# IOIO.net
KiCad netlist of a schematic drawn in EAGLE
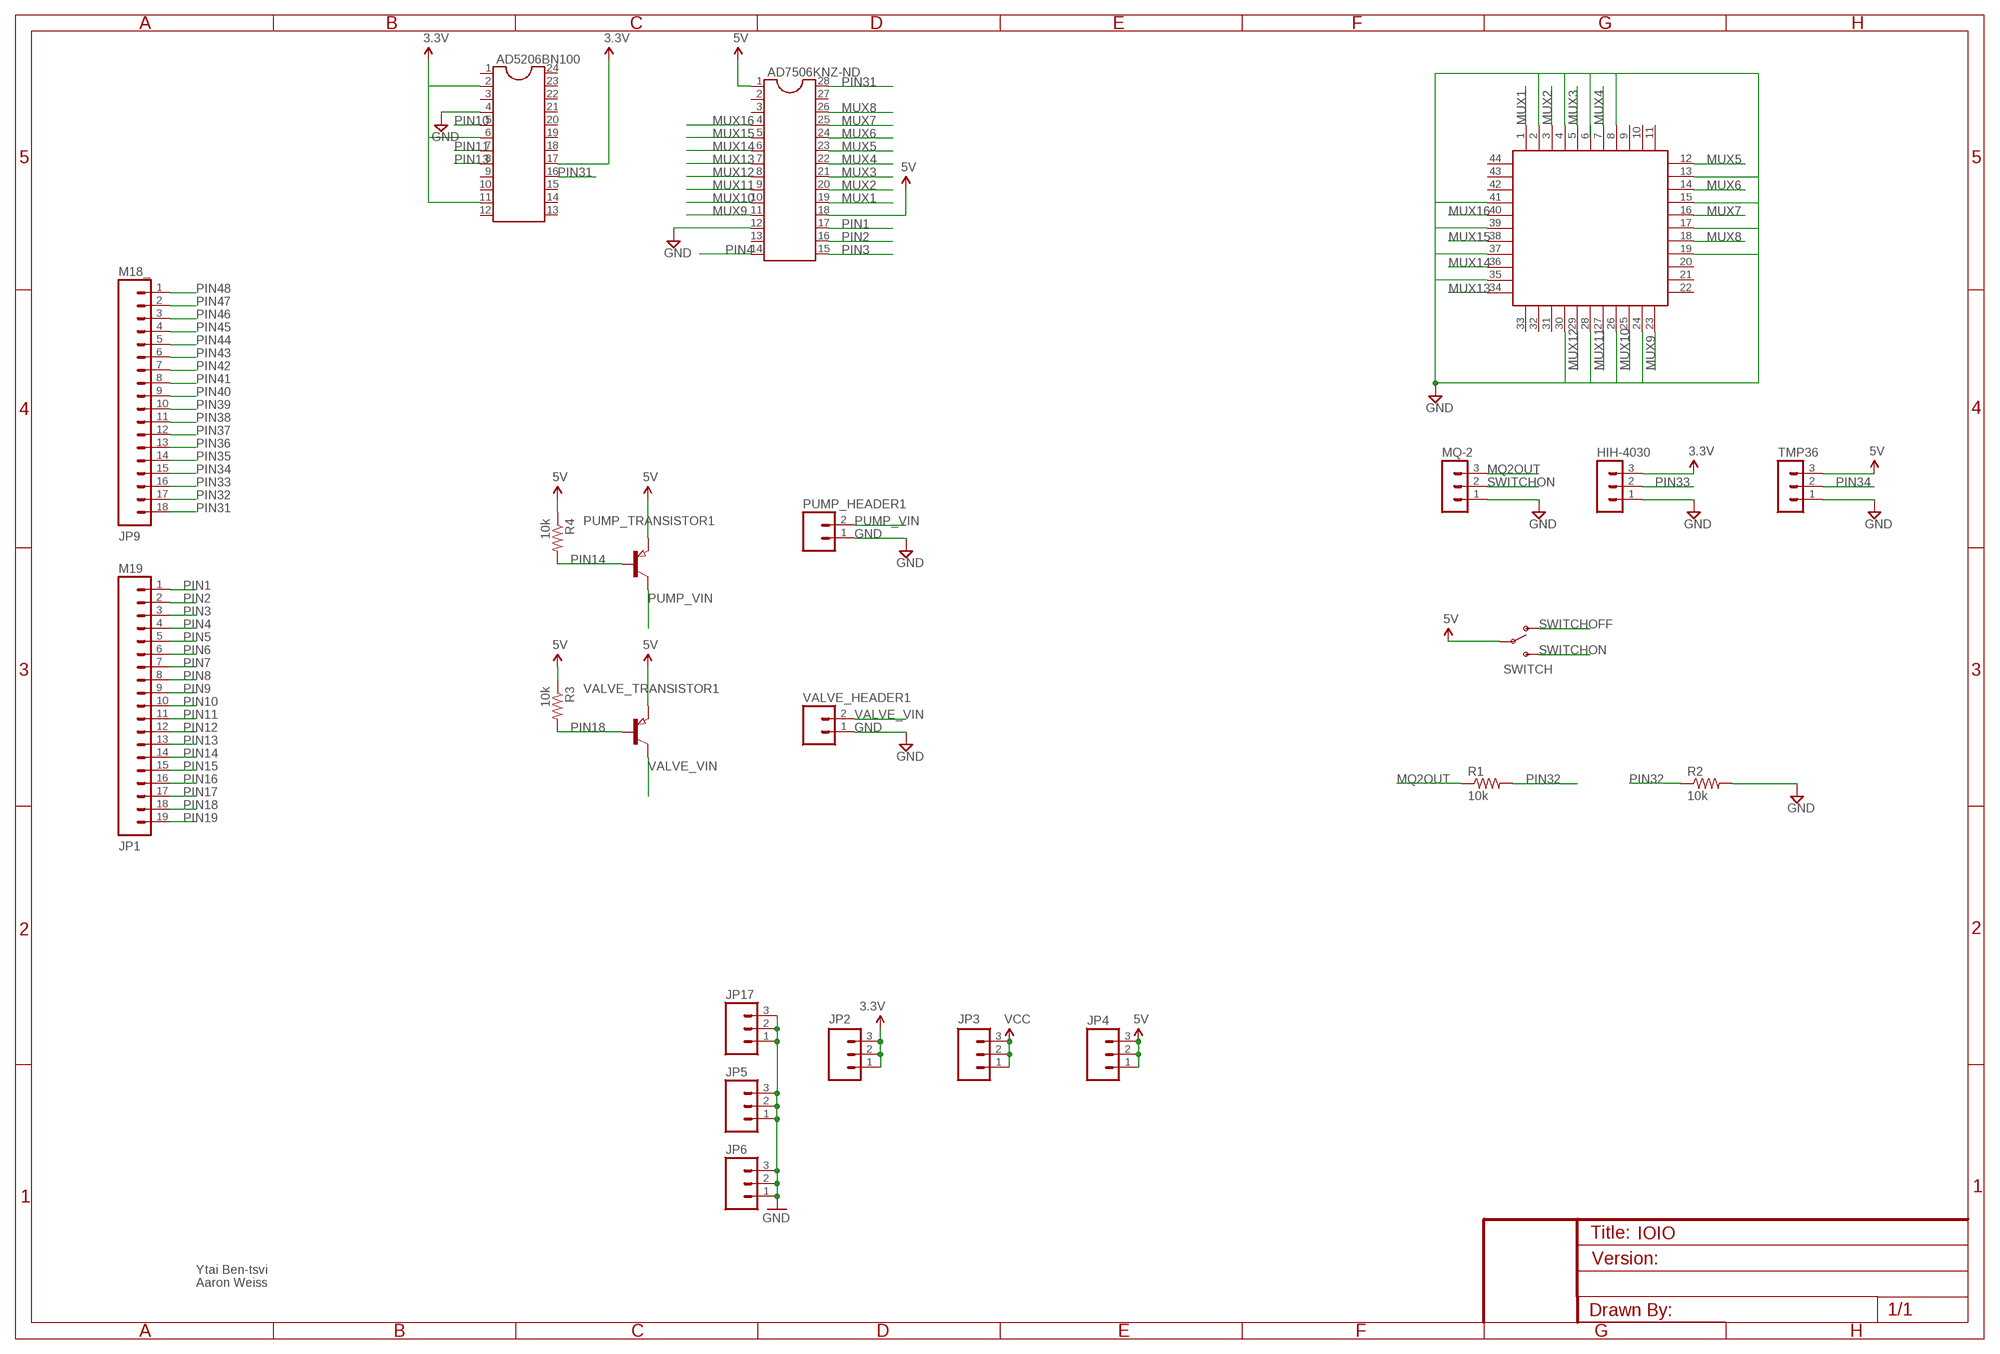
[diagram p0: schematic, sheet 1]

(export (version "E")
  (design (tool "Eeschema 10.0.6"))
  (components
    (comp (ref "AD5206BN100")
      (value "DIL24-3")
      (footprint "eagle-import:DIL24-3")
      (libsource (lib "eagle-import") (part "DIL24-3"))
    )
    (comp (ref "AD7506KNZ-ND")
      (value "DIL28")
      (footprint "eagle-import:DIL28-6")
      (libsource (lib "eagle-import") (part "DIL28"))
    )
    (comp (ref "HIH-4030")
      (value "MA03-1")
      (footprint "eagle-import:MA03-1")
      (libsource (lib "eagle-import") (part "MA03-1"))
    )
    (comp (ref "JP1")
      (value "M19")
      (footprint "eagle-import:1X19")
      (libsource (lib "eagle-import") (part "M19"))
    )
    (comp (ref "JP2")
      (value "M03PTH")
      (footprint "eagle-import:1X03")
      (libsource (lib "eagle-import") (part "M03PTH"))
    )
    (comp (ref "JP3")
      (value "M03PTH")
      (footprint "eagle-import:1X03")
      (libsource (lib "eagle-import") (part "M03PTH"))
    )
    (comp (ref "JP4")
      (value "M03PTH")
      (footprint "eagle-import:1X03")
      (libsource (lib "eagle-import") (part "M03PTH"))
    )
    (comp (ref "JP5")
      (value "M03PTH")
      (footprint "eagle-import:1X03")
      (libsource (lib "eagle-import") (part "M03PTH"))
    )
    (comp (ref "JP6")
      (value "M03PTH")
      (footprint "eagle-import:1X03")
      (libsource (lib "eagle-import") (part "M03PTH"))
    )
    (comp (ref "JP9")
      (value "M18_")
      (footprint "eagle-import:1X18")
      (libsource (lib "eagle-import") (part "M18_"))
    )
    (comp (ref "JP17")
      (value "M03PTH")
      (footprint "eagle-import:1X03")
      (libsource (lib "eagle-import") (part "M03PTH"))
    )
    (comp (ref "MQ-2")
      (value "MA03-1")
      (footprint "eagle-import:MA03-1")
      (libsource (lib "eagle-import") (part "MA03-1"))
    )
    (comp (ref "PUMP_HEADER1")
      (value "M02PTH")
      (footprint "eagle-import:1X02")
      (libsource (lib "eagle-import") (part "M02PTH"))
    )
    (comp (ref "PUMP_TRANSISTOR1")
      (value "PNP-TRANSISTOR_SOT23")
      (footprint "eagle-import:SOT23")
      (libsource (lib "eagle-import") (part "PNP-TRANSISTOR_SOT23"))
    )
    (comp (ref "R1")
      (value "10k")
      (footprint "eagle-import:0207_7")
      (libsource (lib "eagle-import") (part "R-US_0207/7"))
    )
    (comp (ref "R2")
      (value "10k")
      (footprint "eagle-import:0207_7")
      (libsource (lib "eagle-import") (part "R-US_0207/7"))
    )
    (comp (ref "R3")
      (value "10k")
      (footprint "eagle-import:M2012")
      (libsource (lib "eagle-import") (part "R-US_M2012"))
    )
    (comp (ref "R4")
      (value "10k")
      (footprint "eagle-import:M2012")
      (libsource (lib "eagle-import") (part "R-US_M2012"))
    )
    (comp (ref "SWITCH")
      (value "SWITCH-SPSTPTH")
      (footprint "eagle-import:SWITCH-SPDT")
      (libsource (lib "eagle-import") (part "SWITCH-SPSTPTH"))
    )
    (comp (ref "TMP36")
      (value "MA03-1")
      (footprint "eagle-import:MA03-1")
      (libsource (lib "eagle-import") (part "MA03-1"))
    )
    (comp (ref "U$1")
      (value "S44")
      (footprint "eagle-import:S44")
      (libsource (lib "eagle-import") (part "S44"))
    )
    (comp (ref "VALVE_HEADER1")
      (value "M02PTH")
      (footprint "eagle-import:1X02")
      (libsource (lib "eagle-import") (part "M02PTH"))
    )
    (comp (ref "VALVE_TRANSISTOR1")
      (value "PNP-TRANSISTOR_SOT23")
      (footprint "eagle-import:SOT23")
      (libsource (lib "eagle-import") (part "PNP-TRANSISTOR_SOT23"))
    )
  )
  (nets
    (net (code "1") (name "/MQ2OUT") (class "Default")
      (node (ref "MQ-2") (pin "3") (pinfunction "3_3") (pintype "passive"))
      (node (ref "R1") (pin "1") (pinfunction "1_1") (pintype "passive"))
    )
    (net (code "2") (name "/MUX1") (class "Default")
      (node (ref "AD7506KNZ-ND") (pin "19") (pinfunction "19_19") (pintype "passive"))
      (node (ref "U$1") (pin "1") (pinfunction "P$1_1") (pintype "bidirectional"))
    )
    (net (code "3") (name "/MUX2") (class "Default")
      (node (ref "AD7506KNZ-ND") (pin "20") (pinfunction "20_20") (pintype "passive"))
      (node (ref "U$1") (pin "3") (pinfunction "P$3_3") (pintype "bidirectional"))
    )
    (net (code "4") (name "/MUX3") (class "Default")
      (node (ref "AD7506KNZ-ND") (pin "21") (pinfunction "21_21") (pintype "passive"))
      (node (ref "U$1") (pin "5") (pinfunction "P$5_5") (pintype "bidirectional"))
    )
    (net (code "5") (name "/MUX4") (class "Default")
      (node (ref "AD7506KNZ-ND") (pin "22") (pinfunction "22_22") (pintype "passive"))
      (node (ref "U$1") (pin "7") (pinfunction "P$7_7") (pintype "bidirectional"))
    )
    (net (code "6") (name "/MUX5") (class "Default")
      (node (ref "AD7506KNZ-ND") (pin "23") (pinfunction "23_23") (pintype "passive"))
      (node (ref "U$1") (pin "12") (pinfunction "P$12_12") (pintype "bidirectional"))
    )
    (net (code "7") (name "/MUX6") (class "Default")
      (node (ref "AD7506KNZ-ND") (pin "24") (pinfunction "24_24") (pintype "passive"))
      (node (ref "U$1") (pin "14") (pinfunction "P$14_14") (pintype "bidirectional"))
    )
    (net (code "8") (name "/MUX7") (class "Default")
      (node (ref "AD7506KNZ-ND") (pin "25") (pinfunction "25_25") (pintype "passive"))
      (node (ref "U$1") (pin "16") (pinfunction "P$16_16") (pintype "bidirectional"))
    )
    (net (code "9") (name "/MUX8") (class "Default")
      (node (ref "AD7506KNZ-ND") (pin "26") (pinfunction "26_26") (pintype "passive"))
      (node (ref "U$1") (pin "18") (pinfunction "P$18_18") (pintype "bidirectional"))
    )
    (net (code "10") (name "/MUX9") (class "Default")
      (node (ref "AD7506KNZ-ND") (pin "11") (pinfunction "11_11") (pintype "passive"))
      (node (ref "U$1") (pin "23") (pinfunction "P$23_23") (pintype "bidirectional"))
    )
    (net (code "11") (name "/MUX10") (class "Default")
      (node (ref "AD7506KNZ-ND") (pin "10") (pinfunction "10_10") (pintype "passive"))
      (node (ref "U$1") (pin "25") (pinfunction "P$25_25") (pintype "bidirectional"))
    )
    (net (code "12") (name "/MUX11") (class "Default")
      (node (ref "AD7506KNZ-ND") (pin "9") (pinfunction "9_9") (pintype "passive"))
      (node (ref "U$1") (pin "27") (pinfunction "P$27_27") (pintype "bidirectional"))
    )
    (net (code "13") (name "/MUX12") (class "Default")
      (node (ref "AD7506KNZ-ND") (pin "8") (pinfunction "8_8") (pintype "passive"))
      (node (ref "U$1") (pin "29") (pinfunction "P$29_29") (pintype "bidirectional"))
    )
    (net (code "14") (name "/MUX13") (class "Default")
      (node (ref "AD7506KNZ-ND") (pin "7") (pinfunction "7_7") (pintype "passive"))
      (node (ref "U$1") (pin "34") (pinfunction "P$34_34") (pintype "bidirectional"))
    )
    (net (code "15") (name "/MUX14") (class "Default")
      (node (ref "AD7506KNZ-ND") (pin "6") (pinfunction "6_6") (pintype "passive"))
      (node (ref "U$1") (pin "36") (pinfunction "P$36_36") (pintype "bidirectional"))
    )
    (net (code "16") (name "/MUX15") (class "Default")
      (node (ref "AD7506KNZ-ND") (pin "5") (pinfunction "5_5") (pintype "passive"))
      (node (ref "U$1") (pin "38") (pinfunction "P$38_38") (pintype "bidirectional"))
    )
    (net (code "17") (name "/MUX16") (class "Default")
      (node (ref "AD7506KNZ-ND") (pin "4") (pinfunction "4_4") (pintype "passive"))
      (node (ref "U$1") (pin "40") (pinfunction "P$40_40") (pintype "bidirectional"))
    )
    (net (code "18") (name "/PIN1") (class "Default")
      (node (ref "AD7506KNZ-ND") (pin "17") (pinfunction "17_17") (pintype "passive"))
      (node (ref "JP1") (pin "1") (pinfunction "1_1") (pintype "passive"))
    )
    (net (code "19") (name "/PIN2") (class "Default")
      (node (ref "AD7506KNZ-ND") (pin "16") (pinfunction "16_16") (pintype "passive"))
      (node (ref "JP1") (pin "2") (pinfunction "2_2") (pintype "passive"))
    )
    (net (code "20") (name "/PIN3") (class "Default")
      (node (ref "AD7506KNZ-ND") (pin "15") (pinfunction "15_15") (pintype "passive"))
      (node (ref "JP1") (pin "3") (pinfunction "3_3") (pintype "passive"))
    )
    (net (code "21") (name "/PIN4") (class "Default")
      (node (ref "AD7506KNZ-ND") (pin "14") (pinfunction "14_14") (pintype "passive"))
      (node (ref "JP1") (pin "4") (pinfunction "4_4") (pintype "passive"))
    )
    (net (code "22") (name "/PIN5") (class "Default")
      (node (ref "JP1") (pin "5") (pinfunction "5_5") (pintype "passive"))
    )
    (net (code "23") (name "/PIN6") (class "Default")
      (node (ref "JP1") (pin "6") (pinfunction "6_6") (pintype "passive"))
    )
    (net (code "24") (name "/PIN7") (class "Default")
      (node (ref "JP1") (pin "7") (pinfunction "7_7") (pintype "passive"))
    )
    (net (code "25") (name "/PIN8") (class "Default")
      (node (ref "JP1") (pin "8") (pinfunction "8_8") (pintype "passive"))
    )
    (net (code "26") (name "/PIN9") (class "Default")
      (node (ref "JP1") (pin "9") (pinfunction "9_9") (pintype "passive"))
    )
    (net (code "27") (name "/PIN10") (class "Default")
      (node (ref "AD5206BN100") (pin "5") (pinfunction "5_5") (pintype "passive"))
      (node (ref "JP1") (pin "10") (pinfunction "10_10") (pintype "passive"))
    )
    (net (code "28") (name "/PIN11") (class "Default")
      (node (ref "AD5206BN100") (pin "7") (pinfunction "7_7") (pintype "passive"))
      (node (ref "JP1") (pin "11") (pinfunction "11_11") (pintype "passive"))
    )
    (net (code "29") (name "/PIN12") (class "Default")
      (node (ref "JP1") (pin "12") (pinfunction "12_12") (pintype "passive"))
    )
    (net (code "30") (name "/PIN13") (class "Default")
      (node (ref "AD5206BN100") (pin "8") (pinfunction "8_8") (pintype "passive"))
      (node (ref "JP1") (pin "13") (pinfunction "13_13") (pintype "passive"))
    )
    (net (code "31") (name "/PIN14") (class "Default")
      (node (ref "JP1") (pin "14") (pinfunction "14_14") (pintype "passive"))
      (node (ref "PUMP_TRANSISTOR1") (pin "1") (pinfunction "B_1") (pintype "passive"))
      (node (ref "R4") (pin "2") (pinfunction "2_2") (pintype "passive"))
    )
    (net (code "32") (name "/PIN15") (class "Default")
      (node (ref "JP1") (pin "15") (pinfunction "15_15") (pintype "passive"))
    )
    (net (code "33") (name "/PIN16") (class "Default")
      (node (ref "JP1") (pin "16") (pinfunction "16_16") (pintype "passive"))
    )
    (net (code "34") (name "/PIN17") (class "Default")
      (node (ref "JP1") (pin "17") (pinfunction "17_17") (pintype "passive"))
    )
    (net (code "35") (name "/PIN18") (class "Default")
      (node (ref "JP1") (pin "18") (pinfunction "18_18") (pintype "passive"))
      (node (ref "R3") (pin "2") (pinfunction "2_2") (pintype "passive"))
      (node (ref "VALVE_TRANSISTOR1") (pin "1") (pinfunction "B_1") (pintype "passive"))
    )
    (net (code "36") (name "/PIN19") (class "Default")
      (node (ref "JP1") (pin "19") (pinfunction "19_19") (pintype "passive"))
    )
    (net (code "37") (name "/PIN31") (class "Default")
      (node (ref "AD5206BN100") (pin "16") (pinfunction "16_16") (pintype "passive"))
      (node (ref "AD7506KNZ-ND") (pin "28") (pinfunction "28_28") (pintype "passive"))
      (node (ref "JP9") (pin "18") (pinfunction "18_18") (pintype "passive"))
    )
    (net (code "38") (name "/PIN32") (class "Default")
      (node (ref "JP9") (pin "17") (pinfunction "17_17") (pintype "passive"))
      (node (ref "R1") (pin "2") (pinfunction "2_2") (pintype "passive"))
      (node (ref "R2") (pin "1") (pinfunction "1_1") (pintype "passive"))
    )
    (net (code "39") (name "/PIN33") (class "Default")
      (node (ref "HIH-4030") (pin "2") (pinfunction "2_2") (pintype "passive"))
      (node (ref "JP9") (pin "16") (pinfunction "16_16") (pintype "passive"))
    )
    (net (code "40") (name "/PIN34") (class "Default")
      (node (ref "JP9") (pin "15") (pinfunction "15_15") (pintype "passive"))
      (node (ref "TMP36") (pin "2") (pinfunction "2_2") (pintype "passive"))
    )
    (net (code "41") (name "/PIN35") (class "Default")
      (node (ref "JP9") (pin "14") (pinfunction "14_14") (pintype "passive"))
    )
    (net (code "42") (name "/PIN36") (class "Default")
      (node (ref "JP9") (pin "13") (pinfunction "13_13") (pintype "passive"))
    )
    (net (code "43") (name "/PIN37") (class "Default")
      (node (ref "JP9") (pin "12") (pinfunction "12_12") (pintype "passive"))
    )
    (net (code "44") (name "/PIN38") (class "Default")
      (node (ref "JP9") (pin "11") (pinfunction "11_11") (pintype "passive"))
    )
    (net (code "45") (name "/PIN39") (class "Default")
      (node (ref "JP9") (pin "10") (pinfunction "10_10") (pintype "passive"))
    )
    (net (code "46") (name "/PIN40") (class "Default")
      (node (ref "JP9") (pin "9") (pinfunction "9_9") (pintype "passive"))
    )
    (net (code "47") (name "/PIN41") (class "Default")
      (node (ref "JP9") (pin "8") (pinfunction "8_8") (pintype "passive"))
    )
    (net (code "48") (name "/PIN42") (class "Default")
      (node (ref "JP9") (pin "7") (pinfunction "7_7") (pintype "passive"))
    )
    (net (code "49") (name "/PIN43") (class "Default")
      (node (ref "JP9") (pin "6") (pinfunction "6_6") (pintype "passive"))
    )
    (net (code "50") (name "/PIN44") (class "Default")
      (node (ref "JP9") (pin "5") (pinfunction "5_5") (pintype "passive"))
    )
    (net (code "51") (name "/PIN45") (class "Default")
      (node (ref "JP9") (pin "4") (pinfunction "4_4") (pintype "passive"))
    )
    (net (code "52") (name "/PIN46") (class "Default")
      (node (ref "JP9") (pin "3") (pinfunction "3_3") (pintype "passive"))
    )
    (net (code "53") (name "/PIN47") (class "Default")
      (node (ref "JP9") (pin "2") (pinfunction "2_2") (pintype "passive"))
    )
    (net (code "54") (name "/PIN48") (class "Default")
      (node (ref "JP9") (pin "1") (pinfunction "1_1") (pintype "passive"))
    )
    (net (code "55") (name "/PUMP_VIN") (class "Default")
      (node (ref "PUMP_HEADER1") (pin "2") (pinfunction "2_2") (pintype "passive"))
      (node (ref "PUMP_TRANSISTOR1") (pin "3") (pinfunction "C_3") (pintype "passive"))
    )
    (net (code "56") (name "/SWITCHOFF") (class "Default")
      (node (ref "SWITCH") (pin "1") (pinfunction "O_1") (pintype "passive"))
    )
    (net (code "57") (name "/SWITCHON") (class "Default")
      (node (ref "MQ-2") (pin "2") (pinfunction "2_2") (pintype "passive"))
      (node (ref "SWITCH") (pin "3") (pinfunction "S_3") (pintype "passive"))
    )
    (net (code "58") (name "/VALVE_VIN") (class "Default")
      (node (ref "VALVE_HEADER1") (pin "2") (pinfunction "2_2") (pintype "passive"))
      (node (ref "VALVE_TRANSISTOR1") (pin "3") (pinfunction "C_3") (pintype "passive"))
    )
    (net (code "59") (name "3.3V") (class "Default")
      (node (ref "AD5206BN100") (pin "11") (pinfunction "11_11") (pintype "passive"))
      (node (ref "AD5206BN100") (pin "17") (pinfunction "17_17") (pintype "passive"))
      (node (ref "AD5206BN100") (pin "2") (pinfunction "2_2") (pintype "passive"))
      (node (ref "AD5206BN100") (pin "6") (pinfunction "6_6") (pintype "passive"))
      (node (ref "HIH-4030") (pin "3") (pinfunction "3_3") (pintype "passive"))
      (node (ref "JP2") (pin "1") (pinfunction "1_1") (pintype "passive"))
      (node (ref "JP2") (pin "2") (pinfunction "2_2") (pintype "passive"))
      (node (ref "JP2") (pin "3") (pinfunction "3_3") (pintype "passive"))
    )
    (net (code "60") (name "5V") (class "Default")
      (node (ref "AD7506KNZ-ND") (pin "1") (pinfunction "1_1") (pintype "passive"))
      (node (ref "AD7506KNZ-ND") (pin "18") (pinfunction "18_18") (pintype "passive"))
      (node (ref "JP4") (pin "1") (pinfunction "1_1") (pintype "passive"))
      (node (ref "JP4") (pin "2") (pinfunction "2_2") (pintype "passive"))
      (node (ref "JP4") (pin "3") (pinfunction "3_3") (pintype "passive"))
      (node (ref "PUMP_TRANSISTOR1") (pin "2") (pinfunction "E_2") (pintype "passive"))
      (node (ref "R3") (pin "1") (pinfunction "1_1") (pintype "passive"))
      (node (ref "R4") (pin "1") (pinfunction "1_1") (pintype "passive"))
      (node (ref "SWITCH") (pin "2") (pinfunction "P_2") (pintype "passive"))
      (node (ref "TMP36") (pin "3") (pinfunction "3_3") (pintype "passive"))
      (node (ref "VALVE_TRANSISTOR1") (pin "2") (pinfunction "E_2") (pintype "passive"))
    )
    (net (code "61") (name "GND") (class "Default")
      (node (ref "AD5206BN100") (pin "4") (pinfunction "4_4") (pintype "passive"))
      (node (ref "AD7506KNZ-ND") (pin "12") (pinfunction "12_12") (pintype "passive"))
      (node (ref "HIH-4030") (pin "1") (pinfunction "1_1") (pintype "passive"))
      (node (ref "JP17") (pin "1") (pinfunction "1_1") (pintype "passive"))
      (node (ref "JP17") (pin "2") (pinfunction "2_2") (pintype "passive"))
      (node (ref "JP17") (pin "3") (pinfunction "3_3") (pintype "passive"))
      (node (ref "JP5") (pin "1") (pinfunction "1_1") (pintype "passive"))
      (node (ref "JP5") (pin "2") (pinfunction "2_2") (pintype "passive"))
      (node (ref "JP5") (pin "3") (pinfunction "3_3") (pintype "passive"))
      (node (ref "JP6") (pin "1") (pinfunction "1_1") (pintype "passive"))
      (node (ref "JP6") (pin "2") (pinfunction "2_2") (pintype "passive"))
      (node (ref "JP6") (pin "3") (pinfunction "3_3") (pintype "passive"))
      (node (ref "MQ-2") (pin "1") (pinfunction "1_1") (pintype "passive"))
      (node (ref "PUMP_HEADER1") (pin "1") (pinfunction "1_1") (pintype "passive"))
      (node (ref "R2") (pin "2") (pinfunction "2_2") (pintype "passive"))
      (node (ref "TMP36") (pin "1") (pinfunction "1_1") (pintype "passive"))
      (node (ref "U$1") (pin "13") (pinfunction "P$13_13") (pintype "bidirectional"))
      (node (ref "U$1") (pin "15") (pinfunction "P$15_15") (pintype "bidirectional"))
      (node (ref "U$1") (pin "17") (pinfunction "P$17_17") (pintype "bidirectional"))
      (node (ref "U$1") (pin "19") (pinfunction "P$19_19") (pintype "bidirectional"))
      (node (ref "U$1") (pin "2") (pinfunction "P$2_2") (pintype "bidirectional"))
      (node (ref "U$1") (pin "24") (pinfunction "P$24_24") (pintype "bidirectional"))
      (node (ref "U$1") (pin "26") (pinfunction "P$26_26") (pintype "bidirectional"))
      (node (ref "U$1") (pin "28") (pinfunction "P$28_28") (pintype "bidirectional"))
      (node (ref "U$1") (pin "30") (pinfunction "P$30_30") (pintype "bidirectional"))
      (node (ref "U$1") (pin "35") (pinfunction "P$35_35") (pintype "bidirectional"))
      (node (ref "U$1") (pin "37") (pinfunction "P$37_37") (pintype "bidirectional"))
      (node (ref "U$1") (pin "39") (pinfunction "P$39_39") (pintype "bidirectional"))
      (node (ref "U$1") (pin "4") (pinfunction "P$4_4") (pintype "bidirectional"))
      (node (ref "U$1") (pin "41") (pinfunction "P$41_41") (pintype "bidirectional"))
      (node (ref "U$1") (pin "8") (pinfunction "P$8_8") (pintype "bidirectional"))
      (node (ref "VALVE_HEADER1") (pin "1") (pinfunction "1_1") (pintype "passive"))
    )
    (net (code "62") (name "VCC") (class "Default")
      (node (ref "JP3") (pin "1") (pinfunction "1_1") (pintype "passive"))
      (node (ref "JP3") (pin "2") (pinfunction "2_2") (pintype "passive"))
      (node (ref "JP3") (pin "3") (pinfunction "3_3") (pintype "passive"))
    )
    (net (code "63") (name "unconnected-(AD5206BN100-Pad1)") (class "Default")
      (node (ref "AD5206BN100") (pin "1") (pinfunction "1_1") (pintype "passive"))
    )
    (net (code "64") (name "unconnected-(AD5206BN100-Pad3)") (class "Default")
      (node (ref "AD5206BN100") (pin "3") (pinfunction "3_3") (pintype "passive"))
    )
    (net (code "65") (name "unconnected-(AD5206BN100-Pad9)") (class "Default")
      (node (ref "AD5206BN100") (pin "9") (pinfunction "9_9") (pintype "passive"))
    )
    (net (code "66") (name "unconnected-(AD5206BN100-Pad10)") (class "Default")
      (node (ref "AD5206BN100") (pin "10") (pinfunction "10_10") (pintype "passive"))
    )
    (net (code "67") (name "unconnected-(AD5206BN100-Pad12)") (class "Default")
      (node (ref "AD5206BN100") (pin "12") (pinfunction "12_12") (pintype "passive"))
    )
    (net (code "68") (name "unconnected-(AD5206BN100-Pad13)") (class "Default")
      (node (ref "AD5206BN100") (pin "13") (pinfunction "13_13") (pintype "passive"))
    )
    (net (code "69") (name "unconnected-(AD5206BN100-Pad14)") (class "Default")
      (node (ref "AD5206BN100") (pin "14") (pinfunction "14_14") (pintype "passive"))
    )
    (net (code "70") (name "unconnected-(AD5206BN100-Pad15)") (class "Default")
      (node (ref "AD5206BN100") (pin "15") (pinfunction "15_15") (pintype "passive"))
    )
    (net (code "71") (name "unconnected-(AD5206BN100-Pad18)") (class "Default")
      (node (ref "AD5206BN100") (pin "18") (pinfunction "18_18") (pintype "passive"))
    )
    (net (code "72") (name "unconnected-(AD5206BN100-Pad19)") (class "Default")
      (node (ref "AD5206BN100") (pin "19") (pinfunction "19_19") (pintype "passive"))
    )
    (net (code "73") (name "unconnected-(AD5206BN100-Pad20)") (class "Default")
      (node (ref "AD5206BN100") (pin "20") (pinfunction "20_20") (pintype "passive"))
    )
    (net (code "74") (name "unconnected-(AD5206BN100-Pad21)") (class "Default")
      (node (ref "AD5206BN100") (pin "21") (pinfunction "21_21") (pintype "passive"))
    )
    (net (code "75") (name "unconnected-(AD5206BN100-Pad22)") (class "Default")
      (node (ref "AD5206BN100") (pin "22") (pinfunction "22_22") (pintype "passive"))
    )
    (net (code "76") (name "unconnected-(AD5206BN100-Pad23)") (class "Default")
      (node (ref "AD5206BN100") (pin "23") (pinfunction "23_23") (pintype "passive"))
    )
    (net (code "77") (name "unconnected-(AD5206BN100-Pad24)") (class "Default")
      (node (ref "AD5206BN100") (pin "24") (pinfunction "24_24") (pintype "passive"))
    )
    (net (code "78") (name "unconnected-(AD7506KNZ-ND-Pad2)") (class "Default")
      (node (ref "AD7506KNZ-ND") (pin "2") (pinfunction "2_2") (pintype "passive"))
    )
    (net (code "79") (name "unconnected-(AD7506KNZ-ND-Pad3)") (class "Default")
      (node (ref "AD7506KNZ-ND") (pin "3") (pinfunction "3_3") (pintype "passive"))
    )
    (net (code "80") (name "unconnected-(AD7506KNZ-ND-Pad13)") (class "Default")
      (node (ref "AD7506KNZ-ND") (pin "13") (pinfunction "13_13") (pintype "passive"))
    )
    (net (code "81") (name "unconnected-(AD7506KNZ-ND-Pad27)") (class "Default")
      (node (ref "AD7506KNZ-ND") (pin "27") (pinfunction "27_27") (pintype "passive"))
    )
    (net (code "82") (name "unconnected-(U$1-P$6-Pad6)") (class "Default")
      (node (ref "U$1") (pin "6") (pinfunction "P$6_6") (pintype "bidirectional"))
    )
    (net (code "83") (name "unconnected-(U$1-P$9-Pad9)") (class "Default")
      (node (ref "U$1") (pin "9") (pinfunction "P$9_9") (pintype "bidirectional"))
    )
    (net (code "84") (name "unconnected-(U$1-P$10-Pad10)") (class "Default")
      (node (ref "U$1") (pin "10") (pinfunction "P$10_10") (pintype "bidirectional"))
    )
    (net (code "85") (name "unconnected-(U$1-P$11-Pad11)") (class "Default")
      (node (ref "U$1") (pin "11") (pinfunction "P$11_11") (pintype "bidirectional"))
    )
    (net (code "86") (name "unconnected-(U$1-P$20-Pad20)") (class "Default")
      (node (ref "U$1") (pin "20") (pinfunction "P$20_20") (pintype "bidirectional"))
    )
    (net (code "87") (name "unconnected-(U$1-P$21-Pad21)") (class "Default")
      (node (ref "U$1") (pin "21") (pinfunction "P$21_21") (pintype "bidirectional"))
    )
    (net (code "88") (name "unconnected-(U$1-P$22-Pad22)") (class "Default")
      (node (ref "U$1") (pin "22") (pinfunction "P$22_22") (pintype "bidirectional"))
    )
    (net (code "89") (name "unconnected-(U$1-P$31-Pad31)") (class "Default")
      (node (ref "U$1") (pin "31") (pinfunction "P$31_31") (pintype "bidirectional"))
    )
    (net (code "90") (name "unconnected-(U$1-P$32-Pad32)") (class "Default")
      (node (ref "U$1") (pin "32") (pinfunction "P$32_32") (pintype "bidirectional"))
    )
    (net (code "91") (name "unconnected-(U$1-P$33-Pad33)") (class "Default")
      (node (ref "U$1") (pin "33") (pinfunction "P$33_33") (pintype "bidirectional"))
    )
    (net (code "92") (name "unconnected-(U$1-P$42-Pad42)") (class "Default")
      (node (ref "U$1") (pin "42") (pinfunction "P$42_42") (pintype "bidirectional"))
    )
    (net (code "93") (name "unconnected-(U$1-P$43-Pad43)") (class "Default")
      (node (ref "U$1") (pin "43") (pinfunction "P$43_43") (pintype "bidirectional"))
    )
    (net (code "94") (name "unconnected-(U$1-P$44-Pad44)") (class "Default")
      (node (ref "U$1") (pin "44") (pinfunction "P$44_44") (pintype "bidirectional"))
    )
  )
)
